# MCU089B_AltRouting_Misc.net
KiCad netlist of a schematic drawn in Altium Designer
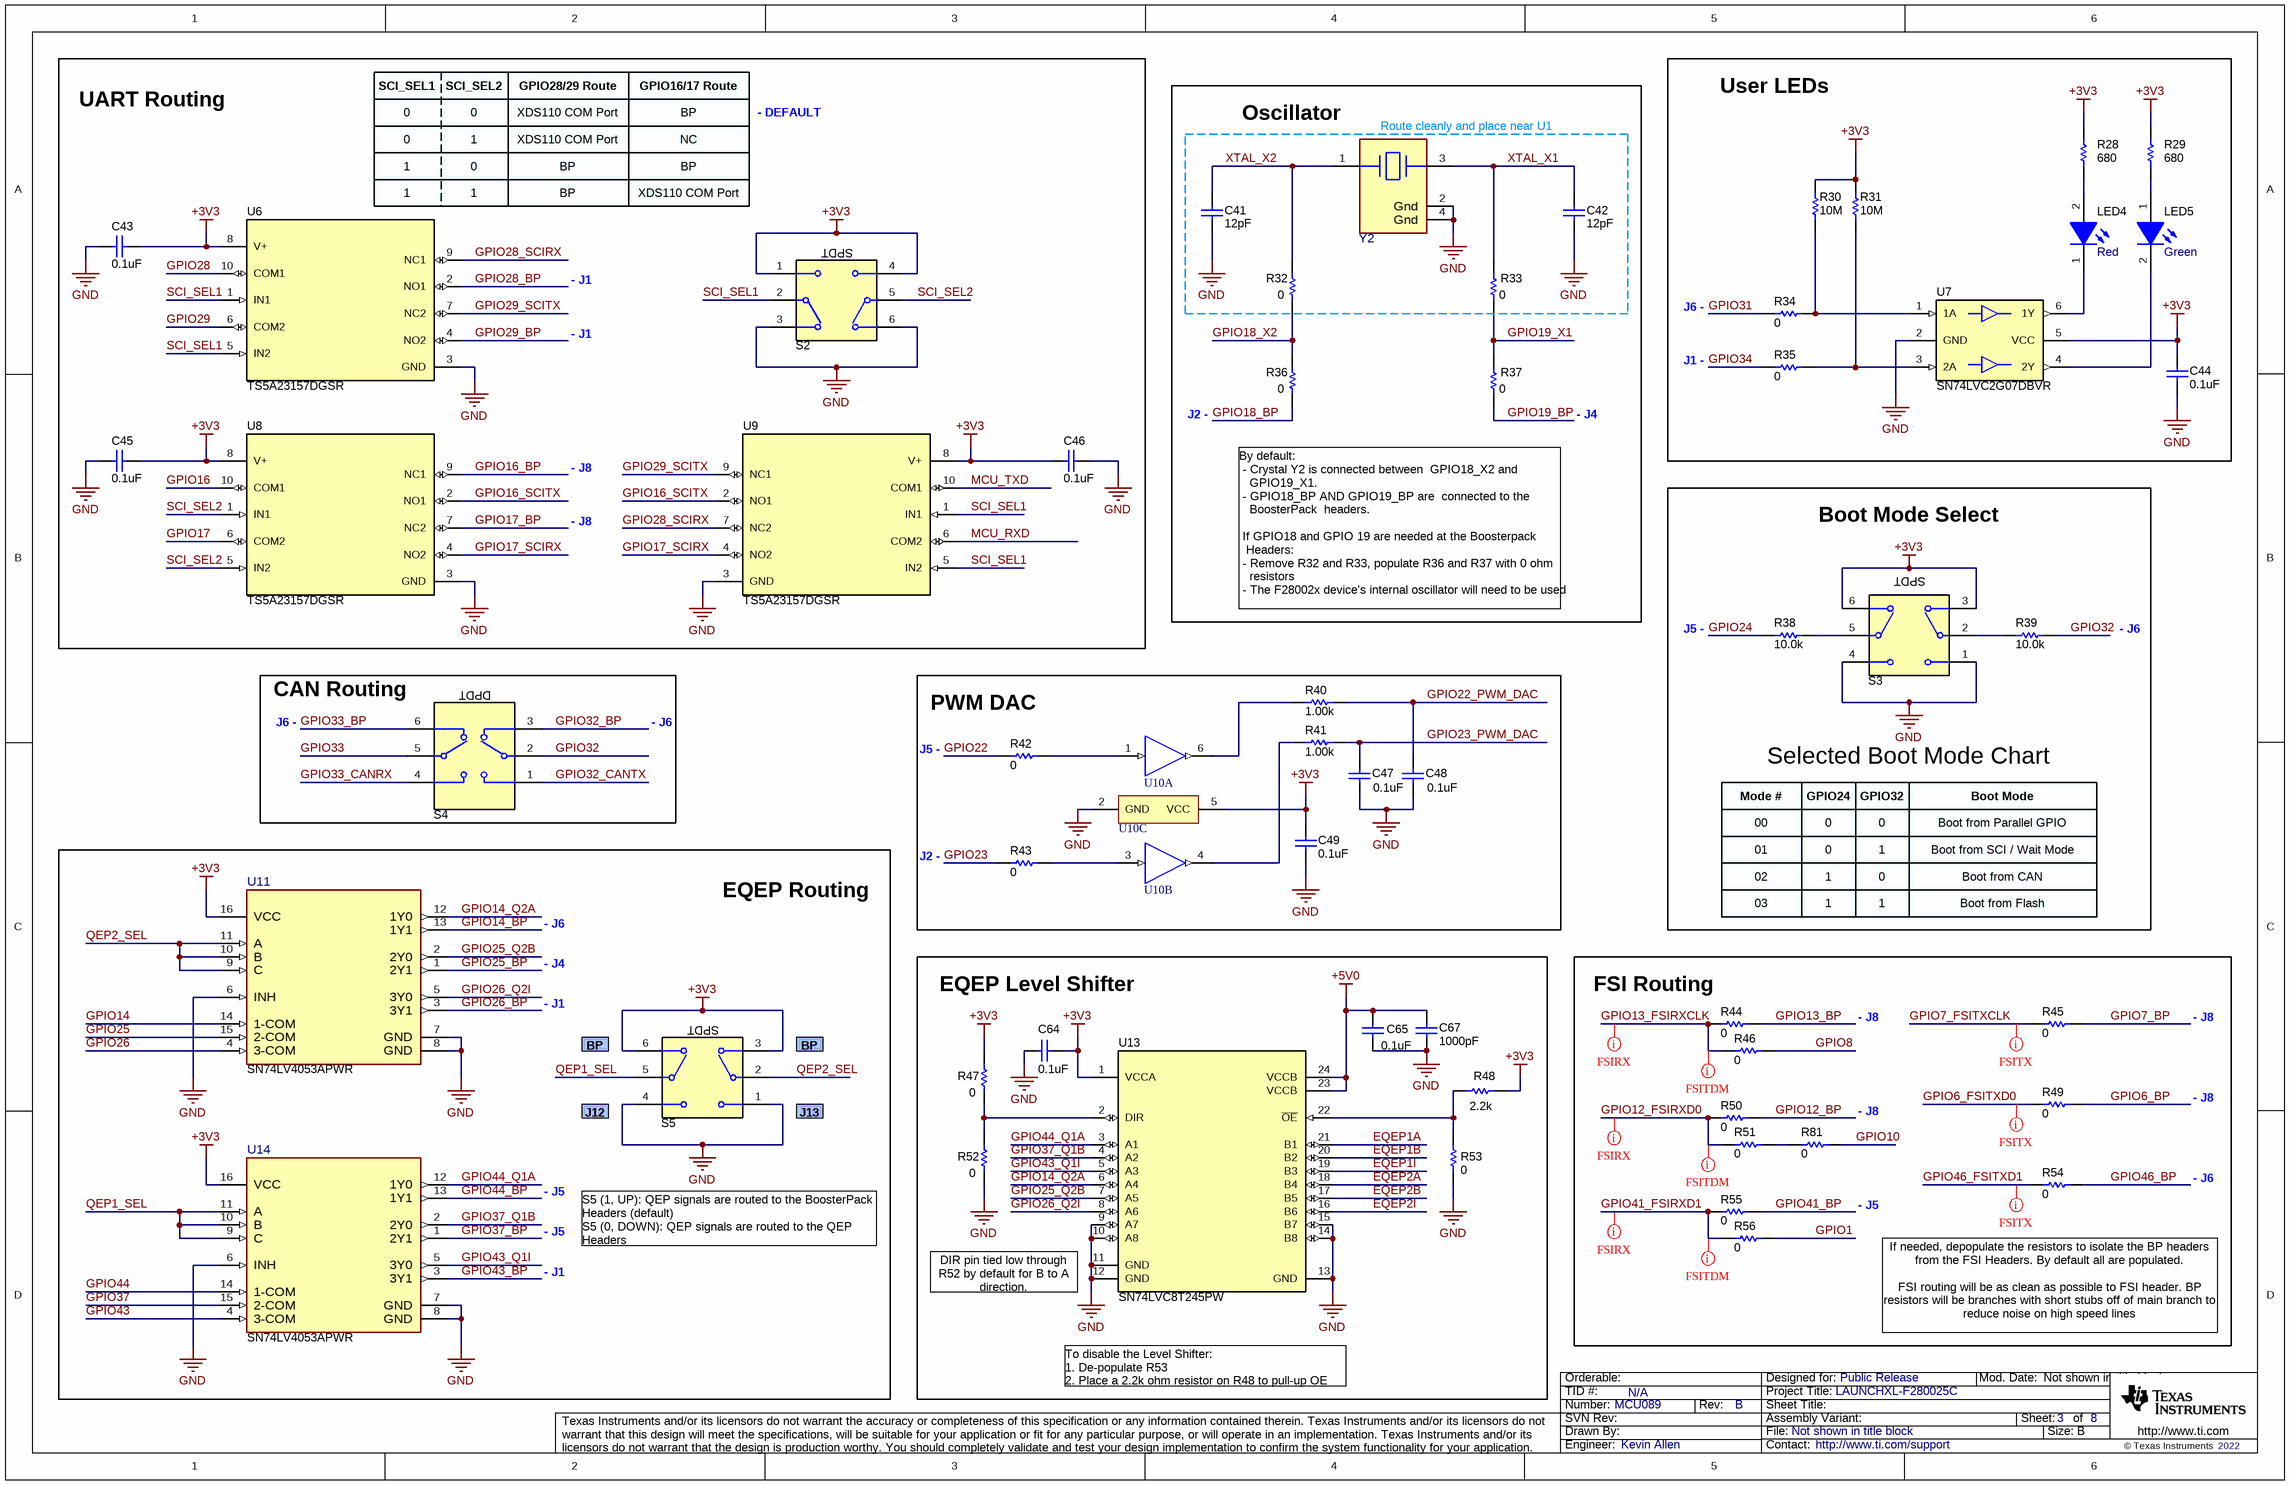
[diagram p0: MCU089B_AltRouting_Misc.SchDoc]

(export (version "E")
  (design (tool "Eeschema 10.0.6"))
  (components
    (comp (ref "C41")
      (value "C0402C120J3GACAUTO")
      (footprint "0402")
      (description "CAP, CERM, 12 pF, 25 V, +/- 5%, C0G/NP0, AEC-Q200 Grade 1, 0402")
      (fields
        (field (name "MANUFACTURER") "Kemet")
        (field (name "VALUEDISPLAYED") "12pF")
        (field (name "PUBLISHER") "Texas Instruments")
      )
      (libsource (lib "Altium Vault - TI") (part "Capacitor"))
    )
    (comp (ref "C42")
      (value "C0402C120J3GACAUTO")
      (footprint "0402")
      (description "CAP, CERM, 12 pF, 25 V, +/- 5%, C0G/NP0, AEC-Q200 Grade 1, 0402")
      (fields
        (field (name "MANUFACTURER") "Kemet")
        (field (name "VALUEDISPLAYED") "12pF")
        (field (name "PUBLISHER") "Texas Instruments")
      )
      (libsource (lib "Altium Vault - TI") (part "Capacitor"))
    )
    (comp (ref "C43")
      (value "GRM155R71A104KA01D")
      (footprint "0402")
      (description "CAP, CERM, 0.1 uF, 10 V, +/- 10%, X7R, 0402")
      (fields
        (field (name "VALUEDISPLAYED") "0.1uF")
        (field (name "MANUFACTURER") "MuRata")
        (field (name "PUBLISHER") "Texas Instruments")
      )
      (libsource (lib "Altium Vault - TI") (part "Capacitor"))
    )
    (comp (ref "C44")
      (value "GRM155R71A104KA01D")
      (footprint "0402")
      (description "CAP, CERM, 0.1 uF, 10 V, +/- 10%, X7R, 0402")
      (fields
        (field (name "VALUEDISPLAYED") "0.1uF")
        (field (name "MANUFACTURER") "MuRata")
        (field (name "PUBLISHER") "Texas Instruments")
      )
      (libsource (lib "Altium Vault - TI") (part "Capacitor"))
    )
    (comp (ref "C45")
      (value "GRM155R71A104KA01D")
      (footprint "0402")
      (description "CAP, CERM, 0.1 uF, 10 V, +/- 10%, X7R, 0402")
      (fields
        (field (name "VALUEDISPLAYED") "0.1uF")
        (field (name "MANUFACTURER") "MuRata")
        (field (name "PUBLISHER") "Texas Instruments")
      )
      (libsource (lib "Altium Vault - TI") (part "Capacitor"))
    )
    (comp (ref "C46")
      (value "GRM155R71A104KA01D")
      (footprint "0402")
      (description "CAP, CERM, 0.1 uF, 10 V, +/- 10%, X7R, 0402")
      (fields
        (field (name "VALUEDISPLAYED") "0.1uF")
        (field (name "MANUFACTURER") "MuRata")
        (field (name "PUBLISHER") "Texas Instruments")
      )
      (libsource (lib "Altium Vault - TI") (part "Capacitor"))
    )
    (comp (ref "C47")
      (value "TMK105B7104MV-FR")
      (footprint "0402")
      (description "CAP, CERM, 0.1 uF, 25 V, +/- 20%, X7R, 0402")
      (fields
        (field (name "MANUFACTURER") "Taiyo Yuden")
        (field (name "VALUEDISPLAYED") "0.1uF")
        (field (name "PUBLISHER") "Texas Instruments")
      )
      (libsource (lib "Altium Vault - TI") (part "Capacitor"))
    )
    (comp (ref "C48")
      (value "TMK105B7104MV-FR")
      (footprint "0402")
      (description "CAP, CERM, 0.1 uF, 25 V, +/- 20%, X7R, 0402")
      (fields
        (field (name "MANUFACTURER") "Taiyo Yuden")
        (field (name "VALUEDISPLAYED") "0.1uF")
        (field (name "PUBLISHER") "Texas Instruments")
      )
      (libsource (lib "Altium Vault - TI") (part "Capacitor"))
    )
    (comp (ref "C49")
      (value "GRM155R71A104KA01D")
      (footprint "0402")
      (description "CAP, CERM, 0.1 uF, 10 V, +/- 10%, X7R, 0402")
      (fields
        (field (name "VALUEDISPLAYED") "0.1uF")
        (field (name "MANUFACTURER") "MuRata")
        (field (name "PUBLISHER") "Texas Instruments")
      )
      (libsource (lib "Altium Vault - TI") (part "Capacitor"))
    )
    (comp (ref "C64")
      (value "GRM155R71A104KA01D")
      (footprint "0402")
      (description "CAP, CERM, 0.1 uF, 10 V, +/- 10%, X7R, 0402")
      (fields
        (field (name "VALUEDISPLAYED") "0.1uF")
        (field (name "MANUFACTURER") "MuRata")
        (field (name "PUBLISHER") "Texas Instruments")
      )
      (libsource (lib "Altium Vault - TI") (part "Capacitor"))
    )
    (comp (ref "C65")
      (value "GRM155R71A104KA01D")
      (footprint "0402")
      (description "CAP, CERM, 0.1 uF, 10 V, +/- 10%, X7R, 0402")
      (fields
        (field (name "VALUEDISPLAYED") "0.1uF")
        (field (name "MANUFACTURER") "MuRata")
        (field (name "PUBLISHER") "Texas Instruments")
      )
      (libsource (lib "Altium Vault - TI") (part "Capacitor"))
    )
    (comp (ref "C67")
      (value "885012205061")
      (footprint "0402")
      (description "CAP, CERM, 1000 pF, 50 V, +/- 10%, X7R, 0402")
      (fields
        (field (name "VALUEDISPLAYED") "1000pF")
        (field (name "MANUFACTURER") "Wurth Elektronik")
        (field (name "PUBLISHER") "Texas Instruments")
      )
      (libsource (lib "Altium Vault - TI") (part "Capacitor"))
    )
    (comp (ref "LED4")
      (value "Red")
      (footprint "WL-SMCW_RED_0805")
      (description "LED, Red, SMD")
      (fields (field (name "MANUFACTURER") "Wurth Elektronik") (field (name "PARTNUMBER") "150080SS75000"))
      (libsource (lib "Altium Vault - TI") (part "LED_A2_K1"))
    )
    (comp (ref "LED5")
      (value "Green")
      (footprint "LED_LTST-C171")
      (description "LED, Green, SMD")
      (fields (field (name "MANUFACTURER") "Lite-On") (field (name "PARTNUMBER") "LTST-C171GKT"))
      (libsource (lib "Altium Vault - TI") (part "LED"))
    )
    (comp (ref "R28")
      (value "CRCW0402680RJNED")
      (footprint "0402")
      (description "RES, 680, 5%, 0.063 W, AEC-Q200 Grade 0, 0402")
      (fields (field (name "MANUFACTURER") "Vishay-Dale") (field (name "VALUEDISPLAYED") "680"))
      (libsource (lib "Altium Vault - TI") (part "CMP-0026962-3"))
    )
    (comp (ref "R29")
      (value "CRCW0402680RJNED")
      (footprint "0402")
      (description "RES, 680, 5%, 0.063 W, AEC-Q200 Grade 0, 0402")
      (fields (field (name "MANUFACTURER") "Vishay-Dale") (field (name "VALUEDISPLAYED") "680"))
      (libsource (lib "Altium Vault - TI") (part "CMP-0026962-3"))
    )
    (comp (ref "R30")
      (value "CRCW040210M0JNED")
      (footprint "0402")
      (description "RES, 10 M, 5%, 0.063 W, AEC-Q200 Grade 0, 0402")
      (fields (field (name "VALUEDISPLAYED") "10M") (field (name "MANUFACTURER") "Vishay-Dale"))
      (libsource (lib "Altium Vault - TI") (part "Resistor"))
    )
    (comp (ref "R31")
      (value "CRCW040210M0JNED")
      (footprint "0402")
      (description "RES, 10 M, 5%, 0.063 W, AEC-Q200 Grade 0, 0402")
      (fields (field (name "VALUEDISPLAYED") "10M") (field (name "MANUFACTURER") "Vishay-Dale"))
      (libsource (lib "Altium Vault - TI") (part "Resistor"))
    )
    (comp (ref "R32")
      (value "CRCW06030000Z0EA")
      (footprint "0603")
      (description "RES, 0, 5%, 0.1 W, AEC-Q200 Grade 0, 0603")
      (fields (field (name "VALUEDISPLAYED") "0") (field (name "MANUFACTURER") "Vishay-Dale"))
      (libsource (lib "Altium Vault - TI") (part "Resistor"))
    )
    (comp (ref "R33")
      (value "CRCW06030000Z0EA")
      (footprint "0603")
      (description "RES, 0, 5%, 0.1 W, AEC-Q200 Grade 0, 0603")
      (fields (field (name "VALUEDISPLAYED") "0") (field (name "MANUFACTURER") "Vishay-Dale"))
      (libsource (lib "Altium Vault - TI") (part "Resistor"))
    )
    (comp (ref "R34")
      (value "CRCW06030000Z0EA")
      (footprint "0603")
      (description "RES, 0, 5%, 0.1 W, AEC-Q200 Grade 0, 0603")
      (fields (field (name "VALUEDISPLAYED") "0") (field (name "MANUFACTURER") "Vishay-Dale"))
      (libsource (lib "Altium Vault - TI") (part "Resistor"))
    )
    (comp (ref "R35")
      (value "CRCW06030000Z0EA")
      (footprint "0603")
      (description "RES, 0, 5%, 0.1 W, AEC-Q200 Grade 0, 0603")
      (fields (field (name "VALUEDISPLAYED") "0") (field (name "MANUFACTURER") "Vishay-Dale"))
      (libsource (lib "Altium Vault - TI") (part "Resistor"))
    )
    (comp (ref "R36")
      (value "CRCW06030000Z0EA")
      (footprint "0603")
      (description "RES, 0, 5%, 0.1 W, AEC-Q200 Grade 0, 0603")
      (fields (field (name "VALUEDISPLAYED") "0") (field (name "MANUFACTURER") "Vishay-Dale"))
      (libsource (lib "Altium Vault - TI") (part "Resistor"))
    )
    (comp (ref "R37")
      (value "CRCW06030000Z0EA")
      (footprint "0603")
      (description "RES, 0, 5%, 0.1 W, AEC-Q200 Grade 0, 0603")
      (fields (field (name "VALUEDISPLAYED") "0") (field (name "MANUFACTURER") "Vishay-Dale"))
      (libsource (lib "Altium Vault - TI") (part "Resistor"))
    )
    (comp (ref "R38")
      (value "RC0603FR-0710KL")
      (footprint "0603")
      (description "RES, 10.0 k, 1%, 0.1 W, 0603")
      (fields (field (name "MANUFACTURER") "Yageo") (field (name "VALUEDISPLAYED") "10.0k"))
      (libsource (lib "Altium Vault - TI") (part "Resistor"))
    )
    (comp (ref "R39")
      (value "RC0603FR-0710KL")
      (footprint "0603")
      (description "RES, 10.0 k, 1%, 0.1 W, 0603")
      (fields (field (name "MANUFACTURER") "Yageo") (field (name "VALUEDISPLAYED") "10.0k"))
      (libsource (lib "Altium Vault - TI") (part "Resistor"))
    )
    (comp (ref "R40")
      (value "CRCW04021K00FKED")
      (footprint "0402")
      (description "RES, 1.00 k, 1%, 0.063 W, AEC-Q200 Grade 0, 0402")
      (fields (field (name "MANUFACTURER") "Vishay-Dale") (field (name "VALUEDISPLAYED") "1.00k"))
      (libsource (lib "Altium Vault - TI") (part "Resistor"))
    )
    (comp (ref "R41")
      (value "CRCW04021K00FKED")
      (footprint "0402")
      (description "RES, 1.00 k, 1%, 0.063 W, AEC-Q200 Grade 0, 0402")
      (fields (field (name "MANUFACTURER") "Vishay-Dale") (field (name "VALUEDISPLAYED") "1.00k"))
      (libsource (lib "Altium Vault - TI") (part "Resistor"))
    )
    (comp (ref "R42")
      (value "CRCW06030000Z0EA")
      (footprint "0603")
      (description "RES, 0, 5%, 0.1 W, AEC-Q200 Grade 0, 0603")
      (fields (field (name "VALUEDISPLAYED") "0") (field (name "MANUFACTURER") "Vishay-Dale"))
      (libsource (lib "Altium Vault - TI") (part "Resistor"))
    )
    (comp (ref "R43")
      (value "CRCW06030000Z0EA")
      (footprint "0603")
      (description "RES, 0, 5%, 0.1 W, AEC-Q200 Grade 0, 0603")
      (fields (field (name "VALUEDISPLAYED") "0") (field (name "MANUFACTURER") "Vishay-Dale"))
      (libsource (lib "Altium Vault - TI") (part "Resistor"))
    )
    (comp (ref "R44")
      (value "CRCW06030000Z0EA")
      (footprint "0603")
      (description "RES, 0, 5%, 0.1 W, AEC-Q200 Grade 0, 0603")
      (fields (field (name "VALUEDISPLAYED") "0") (field (name "MANUFACTURER") "Vishay-Dale"))
      (libsource (lib "Altium Vault - TI") (part "Resistor"))
    )
    (comp (ref "R45")
      (value "CRCW06030000Z0EA")
      (footprint "0603")
      (description "RES, 0, 5%, 0.1 W, AEC-Q200 Grade 0, 0603")
      (fields (field (name "VALUEDISPLAYED") "0") (field (name "MANUFACTURER") "Vishay-Dale"))
      (libsource (lib "Altium Vault - TI") (part "Resistor"))
    )
    (comp (ref "R46")
      (value "CRCW06030000Z0EA")
      (footprint "0603")
      (description "RES, 0, 5%, 0.1 W, AEC-Q200 Grade 0, 0603")
      (fields (field (name "VALUEDISPLAYED") "0") (field (name "MANUFACTURER") "Vishay-Dale"))
      (libsource (lib "Altium Vault - TI") (part "Resistor"))
    )
    (comp (ref "R47")
      (value "CRCW06030000Z0EA")
      (footprint "0603")
      (description "RES, 0, 5%, 0.1 W, AEC-Q200 Grade 0, 0603")
      (fields (field (name "VALUEDISPLAYED") "0") (field (name "MANUFACTURER") "Vishay-Dale"))
      (libsource (lib "Altium Vault - TI") (part "Resistor"))
    )
    (comp (ref "R48")
      (value "CRCW06032K20JNEA")
      (footprint "0603")
      (description "RES, 2.2 k, 5%, 0.1 W, AEC-Q200 Grade 0, 0603")
      (fields (field (name "VALUEDISPLAYED") "2.2k") (field (name "MANUFACTURER") "Vishay-Dale"))
      (libsource (lib "Altium Vault - TI") (part "Resistor"))
    )
    (comp (ref "R49")
      (value "CRCW06030000Z0EA")
      (footprint "0603")
      (description "RES, 0, 5%, 0.1 W, AEC-Q200 Grade 0, 0603")
      (fields (field (name "VALUEDISPLAYED") "0") (field (name "MANUFACTURER") "Vishay-Dale"))
      (libsource (lib "Altium Vault - TI") (part "Resistor"))
    )
    (comp (ref "R50")
      (value "CRCW06030000Z0EA")
      (footprint "0603")
      (description "RES, 0, 5%, 0.1 W, AEC-Q200 Grade 0, 0603")
      (fields (field (name "VALUEDISPLAYED") "0") (field (name "MANUFACTURER") "Vishay-Dale"))
      (libsource (lib "Altium Vault - TI") (part "Resistor"))
    )
    (comp (ref "R51")
      (value "CRCW06030000Z0EA")
      (footprint "0603")
      (description "RES, 0, 5%, 0.1 W, AEC-Q200 Grade 0, 0603")
      (fields (field (name "VALUEDISPLAYED") "0") (field (name "MANUFACTURER") "Vishay-Dale"))
      (libsource (lib "Altium Vault - TI") (part "Resistor"))
    )
    (comp (ref "R52")
      (value "CRCW06030000Z0EA")
      (footprint "0603")
      (description "RES, 0, 5%, 0.1 W, AEC-Q200 Grade 0, 0603")
      (fields (field (name "VALUEDISPLAYED") "0") (field (name "MANUFACTURER") "Vishay-Dale"))
      (libsource (lib "Altium Vault - TI") (part "Resistor"))
    )
    (comp (ref "R53")
      (value "CRCW06030000Z0EA")
      (footprint "0603")
      (description "RES, 0, 5%, 0.1 W, AEC-Q200 Grade 0, 0603")
      (fields (field (name "VALUEDISPLAYED") "0") (field (name "MANUFACTURER") "Vishay-Dale"))
      (libsource (lib "Altium Vault - TI") (part "Resistor"))
    )
    (comp (ref "R54")
      (value "CRCW06030000Z0EA")
      (footprint "0603")
      (description "RES, 0, 5%, 0.1 W, AEC-Q200 Grade 0, 0603")
      (fields (field (name "VALUEDISPLAYED") "0") (field (name "MANUFACTURER") "Vishay-Dale"))
      (libsource (lib "Altium Vault - TI") (part "Resistor"))
    )
    (comp (ref "R55")
      (value "CRCW06030000Z0EA")
      (footprint "0603")
      (description "RES, 0, 5%, 0.1 W, AEC-Q200 Grade 0, 0603")
      (fields (field (name "VALUEDISPLAYED") "0") (field (name "MANUFACTURER") "Vishay-Dale"))
      (libsource (lib "Altium Vault - TI") (part "Resistor"))
    )
    (comp (ref "R56")
      (value "CRCW06030000Z0EA")
      (footprint "0603")
      (description "RES, 0, 5%, 0.1 W, AEC-Q200 Grade 0, 0603")
      (fields (field (name "VALUEDISPLAYED") "0") (field (name "MANUFACTURER") "Vishay-Dale"))
      (libsource (lib "Altium Vault - TI") (part "Resistor"))
    )
    (comp (ref "R81")
      (value "CRCW06030000Z0EA")
      (footprint "0603")
      (description "RES, 0, 5%, 0.1 W, AEC-Q200 Grade 0, 0603")
      (fields (field (name "VALUEDISPLAYED") "0") (field (name "MANUFACTURER") "Vishay-Dale"))
      (libsource (lib "Altium Vault - TI") (part "Resistor"))
    )
    (comp (ref "S2")
      (value "CAS-D20TA")
      (footprint "SW_CAS-D20TA")
      (description "Switch, Dual SPDT,  2 Pos, 0.1A, 6VDC, SMD")
      (fields
        (field (name "MANUFACTURER") "Copal Electronics")
        (field (name "PUBLISHER") "Texas Instruments")
      )
      (libsource (lib "Altium Vault - TI") (part "SW_SPDT_CAS-D20TA"))
    )
    (comp (ref "S3")
      (value "CAS-D20TA")
      (footprint "SW_CAS-D20TA")
      (description "Switch, Dual SPDT,  2 Pos, 0.1A, 6VDC, SMD")
      (fields
        (field (name "MANUFACTURER") "Copal Electronics")
        (field (name "PUBLISHER") "Texas Instruments")
      )
      (libsource (lib "") (part "SW_SPDT_CAS-D20TA_1"))
    )
    (comp (ref "S4")
      (value "CAS-220TA")
      (footprint "SW_CAS-220TA")
      (description "SLIDE SWITCH DPDT  .1A, SMT")
      (fields
        (field (name "MANUFACTURER") "Copal Electronics")
        (field (name "PUBLISHER") "Texas Instruments")
      )
      (libsource (lib "Altium Vault - TI") (part "SW_CAS-220TA"))
    )
    (comp (ref "S5")
      (value "CAS-D20TA")
      (footprint "SW_CAS-D20TA")
      (description "Switch, Dual SPDT,  2 Pos, 0.1A, 6VDC, SMD")
      (fields
        (field (name "MANUFACTURER") "Copal Electronics")
        (field (name "PUBLISHER") "Texas Instruments")
      )
      (libsource (lib "") (part "SW_SPDT_CAS-D20TA_1"))
    )
    (comp (ref "U6")
      (value "TS5A23157DGSR")
      (footprint "DGS0010A_N")
      (description "DUAL 10-Ohm SPDT ANALOG SWITCH, DGS0010A (VSSOP-10)")
      (fields
        (field (name "ALTERNATE PARTNUMBER") "TS5A23157DGST")
        (field (name "MANUFACTURER") "Texas Instruments")
        (field (name "PARTNUMBER") "TS5A23157DGSR")
        (field (name "PUBLISHER") "Texas Instruments")
      )
      (libsource (lib "Altium Vault - TI") (part "TS5A23159"))
    )
    (comp (ref "U7")
      (value "SN74LVC2G07DBVR")
      (footprint "DBV0006A_N")
      (description "Dual Buffer/Driver with Open-Drain Output, DBV0006A, LARGE T&R")
      (fields
        (field (name "GENERIC PART NUMBER") "SN74LVC2G07")
        (field (name "MANUFACTURER") "Texas Instruments")
      )
      (libsource (lib "Altium Vault - TI") (part "CMP-0051789-2"))
    )
    (comp (ref "U8")
      (value "TS5A23157DGSR")
      (footprint "DGS0010A_N")
      (description "DUAL 10-Ohm SPDT ANALOG SWITCH, DGS0010A (VSSOP-10)")
      (fields
        (field (name "ALTERNATE PARTNUMBER") "TS5A23157DGST")
        (field (name "MANUFACTURER") "Texas Instruments")
        (field (name "PARTNUMBER") "TS5A23157DGSR")
        (field (name "PUBLISHER") "Texas Instruments")
      )
      (libsource (lib "Altium Vault - TI") (part "TS5A23159"))
    )
    (comp (ref "U9")
      (value "TS5A23157DGSR")
      (footprint "DGS0010A_N")
      (description "DUAL 10-Ohm SPDT ANALOG SWITCH, DGS0010A (VSSOP-10)")
      (fields
        (field (name "ALTERNATE PARTNUMBER") "TS5A23157DGST")
        (field (name "MANUFACTURER") "Texas Instruments")
        (field (name "PARTNUMBER") "TS5A23157DGSR")
        (field (name "PUBLISHER") "Texas Instruments")
      )
      (libsource (lib "") (part "TS5A23159_1"))
    )
    (comp (ref "U10")
      (value "SN74LVC2G34DBVR")
      (footprint "DBV0006A_N")
      (description "Dual Buffer Gate, DBV0006A, LARGE T&R")
      (fields
        (field (name "MANUFACTURER") "Texas Instruments")
        (field (name "GENERIC PART NUMBER") "SN74LVC2G34")
      )
      (libsource (lib "") (part "TI-SN74XXX2GXXX-6_A_1"))
    )
    (comp (ref "U11")
      (value "SN74LV4053APWR")
      (footprint "PW0016A-MFG")
      (description "3 Circuit IC Switch 2:1 75Ohm 16-TSSOP")
      (fields
        (field (name "PARTNUMBER") "SN74LV4053APWR")
        (field (name "MOUSER PART NUMBER") "595-SN74LV4053APWR")
        (field (name "DIGIKEY PART NUMBER") "296-3833-1-ND")
      )
      (libsource (lib "Altium Vault - TI") (part "SYM-SN74LV4053APWR"))
    )
    (comp (ref "U13")
      (value "SN74LVC8T245PW")
      (footprint "PW0024A_N")
      (fields (field (name "MANUFACTURER") "Texas Instruments") (field (name "PARTNUMBER") "SN74LVC8T245PW"))
      (libsource (lib "Altium Vault - TI") (part "SN74LVC8T245"))
    )
    (comp (ref "U14")
      (value "SN74LV4053APWR")
      (footprint "PW0016A-MFG")
      (description "3 Circuit IC Switch 2:1 75Ohm 16-TSSOP")
      (fields
        (field (name "PARTNUMBER") "SN74LV4053APWR")
        (field (name "MOUSER PART NUMBER") "595-SN74LV4053APWR")
        (field (name "DIGIKEY PART NUMBER") "296-3833-1-ND")
      )
      (libsource (lib "Altium Vault - TI") (part "SYM-SN74LV4053APWR"))
    )
    (comp (ref "Y2")
      (value "ECS-200-8-30B-CKM")
      (footprint "FP-ECS-200-8-30B-CKM_SMD4-MFG")
      (description "20 MHz ±10ppm Crystal 8pF 40 Ohms 4-SMD, No Lead")
      (fields
        (field (name "MOUSER PART NUMBER") "520-200-8-30B-CKM")
        (field (name "MANUFACTURER") "ECS International")
      )
      (libsource (lib "Altium Vault - TI") (part "SYM-ECS-200-8-30B-CKM"))
    )
  )
  (nets
    (net (code "1") (name "+3V3") (class "Default")
      (node (ref "C43") (pin "1") (pinfunction "1_1") (pintype "passive"))
      (node (ref "C44") (pin "2") (pinfunction "2_2") (pintype "passive"))
      (node (ref "C45") (pin "1") (pinfunction "1_1") (pintype "passive"))
      (node (ref "C46") (pin "2") (pinfunction "2_2") (pintype "passive"))
      (node (ref "C49") (pin "2") (pinfunction "2_2") (pintype "passive"))
      (node (ref "C64") (pin "1") (pinfunction "1_1") (pintype "passive"))
      (node (ref "R28") (pin "2") (pinfunction "2_2") (pintype "passive"))
      (node (ref "R29") (pin "2") (pinfunction "2_2") (pintype "passive"))
      (node (ref "R30") (pin "2") (pinfunction "2_2") (pintype "passive"))
      (node (ref "R31") (pin "2") (pinfunction "2_2") (pintype "passive"))
      (node (ref "R47") (pin "2") (pinfunction "2_2") (pintype "passive"))
      (node (ref "R48") (pin "2") (pinfunction "2_2") (pintype "passive"))
      (node (ref "S2") (pin "1") (pinfunction "1_1") (pintype "passive"))
      (node (ref "S2") (pin "4") (pinfunction "4_4") (pintype "passive"))
      (node (ref "S3") (pin "3") (pinfunction "3_3") (pintype "passive"))
      (node (ref "S3") (pin "6") (pinfunction "6_6") (pintype "passive"))
      (node (ref "S5") (pin "3") (pinfunction "3_3") (pintype "passive"))
      (node (ref "S5") (pin "6") (pinfunction "6_6") (pintype "passive"))
      (node (ref "U10") (pin "5") (pinfunction "VCC_5") (pintype "power_in"))
      (node (ref "U11") (pin "16") (pinfunction "VCC_16") (pintype "power_in"))
      (node (ref "U13") (pin "1") (pinfunction "VCCA_1") (pintype "power_in"))
      (node (ref "U14") (pin "16") (pinfunction "VCC_16") (pintype "power_in"))
      (node (ref "U6") (pin "8") (pinfunction "V+_8") (pintype "power_in"))
      (node (ref "U7") (pin "5") (pinfunction "VCC_5") (pintype "power_in"))
      (node (ref "U8") (pin "8") (pinfunction "V+_8") (pintype "power_in"))
      (node (ref "U9") (pin "8") (pinfunction "V+_8") (pintype "power_in"))
    )
    (net (code "2") (name "+5V0") (class "Default")
      (node (ref "C65") (pin "2") (pinfunction "2_2") (pintype "passive"))
      (node (ref "C67") (pin "1") (pinfunction "1_1") (pintype "passive"))
      (node (ref "U13") (pin "23") (pinfunction "VCCB_23") (pintype "power_in"))
      (node (ref "U13") (pin "24") (pinfunction "VCCB_24") (pintype "power_in"))
    )
    (net (code "3") (name "/EQEP1A") (class "Default")
      (node (ref "U13") (pin "21") (pinfunction "B1_21") (pintype "bidirectional"))
    )
    (net (code "4") (name "/EQEP1B") (class "Default")
      (node (ref "U13") (pin "20") (pinfunction "B2_20") (pintype "bidirectional"))
    )
    (net (code "5") (name "/EQEP1I") (class "Default")
      (node (ref "U13") (pin "19") (pinfunction "B3_19") (pintype "bidirectional"))
    )
    (net (code "6") (name "/EQEP2A") (class "Default")
      (node (ref "U13") (pin "18") (pinfunction "B4_18") (pintype "bidirectional"))
    )
    (net (code "7") (name "/EQEP2B") (class "Default")
      (node (ref "U13") (pin "17") (pinfunction "B5_17") (pintype "bidirectional"))
    )
    (net (code "8") (name "/EQEP2I") (class "Default")
      (node (ref "U13") (pin "16") (pinfunction "B6_16") (pintype "bidirectional"))
    )
    (net (code "9") (name "/GPIO1") (class "Default")
      (node (ref "R56") (pin "2") (pinfunction "2_2") (pintype "passive"))
    )
    (net (code "10") (name "/GPIO6_BP") (class "Default")
      (node (ref "R49") (pin "2") (pinfunction "2_2") (pintype "passive"))
    )
    (net (code "11") (name "/GPIO6_FSITXD0") (class "Default")
      (node (ref "R49") (pin "1") (pinfunction "1_1") (pintype "passive"))
    )
    (net (code "12") (name "/GPIO7_BP") (class "Default")
      (node (ref "R45") (pin "2") (pinfunction "2_2") (pintype "passive"))
    )
    (net (code "13") (name "/GPIO7_FSITXCLK") (class "Default")
      (node (ref "R45") (pin "1") (pinfunction "1_1") (pintype "passive"))
    )
    (net (code "14") (name "/GPIO8") (class "Default")
      (node (ref "R46") (pin "2") (pinfunction "2_2") (pintype "passive"))
    )
    (net (code "15") (name "/GPIO10") (class "Default")
      (node (ref "R81") (pin "2") (pinfunction "2_2") (pintype "passive"))
    )
    (net (code "16") (name "/GPIO12_BP") (class "Default")
      (node (ref "R50") (pin "2") (pinfunction "2_2") (pintype "passive"))
    )
    (net (code "17") (name "/GPIO12_FSIRXD0") (class "Default")
      (node (ref "R50") (pin "1") (pinfunction "1_1") (pintype "passive"))
      (node (ref "R51") (pin "1") (pinfunction "1_1") (pintype "passive"))
    )
    (net (code "18") (name "/GPIO13_BP") (class "Default")
      (node (ref "R44") (pin "2") (pinfunction "2_2") (pintype "passive"))
    )
    (net (code "19") (name "/GPIO13_FSIRXCLK") (class "Default")
      (node (ref "R44") (pin "1") (pinfunction "1_1") (pintype "passive"))
      (node (ref "R46") (pin "1") (pinfunction "1_1") (pintype "passive"))
    )
    (net (code "20") (name "/GPIO14") (class "Default")
      (node (ref "U11") (pin "14") (pinfunction "1-COM_14") (pintype "input"))
    )
    (net (code "21") (name "/GPIO14_BP") (class "Default")
      (node (ref "U11") (pin "13") (pinfunction "1Y1_13") (pintype "output"))
    )
    (net (code "22") (name "/GPIO14_Q2A") (class "Default")
      (node (ref "U11") (pin "12") (pinfunction "1Y0_12") (pintype "output"))
      (node (ref "U13") (pin "6") (pinfunction "A4_6") (pintype "bidirectional"))
    )
    (net (code "23") (name "/GPIO16") (class "Default")
      (node (ref "U8") (pin "10") (pinfunction "COM1_10") (pintype "bidirectional"))
    )
    (net (code "24") (name "/GPIO16_BP") (class "Default")
      (node (ref "U8") (pin "9") (pinfunction "NC1_9") (pintype "bidirectional"))
    )
    (net (code "25") (name "/GPIO16_SCITX") (class "Default")
      (node (ref "U8") (pin "2") (pinfunction "NO1_2") (pintype "bidirectional"))
      (node (ref "U9") (pin "2") (pinfunction "NO1_2") (pintype "bidirectional"))
    )
    (net (code "26") (name "/GPIO17") (class "Default")
      (node (ref "U8") (pin "6") (pinfunction "COM2_6") (pintype "bidirectional"))
    )
    (net (code "27") (name "/GPIO17_BP") (class "Default")
      (node (ref "U8") (pin "7") (pinfunction "NC2_7") (pintype "bidirectional"))
    )
    (net (code "28") (name "/GPIO17_SCIRX") (class "Default")
      (node (ref "U8") (pin "4") (pinfunction "NO2_4") (pintype "bidirectional"))
      (node (ref "U9") (pin "4") (pinfunction "NO2_4") (pintype "bidirectional"))
    )
    (net (code "29") (name "/GPIO18_BP") (class "Default")
      (node (ref "R36") (pin "1") (pinfunction "1_1") (pintype "passive"))
    )
    (net (code "30") (name "/GPIO18_X2") (class "Default")
      (node (ref "R32") (pin "1") (pinfunction "1_1") (pintype "passive"))
      (node (ref "R36") (pin "2") (pinfunction "2_2") (pintype "passive"))
    )
    (net (code "31") (name "/GPIO19_BP") (class "Default")
      (node (ref "R37") (pin "1") (pinfunction "1_1") (pintype "passive"))
    )
    (net (code "32") (name "/GPIO19_X1") (class "Default")
      (node (ref "R33") (pin "1") (pinfunction "1_1") (pintype "passive"))
      (node (ref "R37") (pin "2") (pinfunction "2_2") (pintype "passive"))
    )
    (net (code "33") (name "/GPIO22") (class "Default")
      (node (ref "R42") (pin "1") (pinfunction "1_1") (pintype "passive"))
    )
    (net (code "34") (name "/GPIO22_PWM_DAC") (class "Default")
      (node (ref "C48") (pin "1") (pinfunction "1_1") (pintype "passive"))
      (node (ref "R40") (pin "2") (pinfunction "2_2") (pintype "passive"))
    )
    (net (code "35") (name "/GPIO23") (class "Default")
      (node (ref "R43") (pin "1") (pinfunction "1_1") (pintype "passive"))
    )
    (net (code "36") (name "/GPIO23_PWM_DAC") (class "Default")
      (node (ref "C47") (pin "1") (pinfunction "1_1") (pintype "passive"))
      (node (ref "R41") (pin "2") (pinfunction "2_2") (pintype "passive"))
    )
    (net (code "37") (name "/GPIO24") (class "Default")
      (node (ref "R38") (pin "1") (pinfunction "1_1") (pintype "passive"))
    )
    (net (code "38") (name "/GPIO25") (class "Default")
      (node (ref "U11") (pin "15") (pinfunction "2-COM_15") (pintype "input"))
    )
    (net (code "39") (name "/GPIO25_BP") (class "Default")
      (node (ref "U11") (pin "1") (pinfunction "2Y1_1") (pintype "output"))
    )
    (net (code "40") (name "/GPIO25_Q2B") (class "Default")
      (node (ref "U11") (pin "2") (pinfunction "2Y0_2") (pintype "output"))
      (node (ref "U13") (pin "7") (pinfunction "A5_7") (pintype "bidirectional"))
    )
    (net (code "41") (name "/GPIO26") (class "Default")
      (node (ref "U11") (pin "4") (pinfunction "3-COM_4") (pintype "input"))
    )
    (net (code "42") (name "/GPIO26_BP") (class "Default")
      (node (ref "U11") (pin "3") (pinfunction "3Y1_3") (pintype "output"))
    )
    (net (code "43") (name "/GPIO26_Q2I") (class "Default")
      (node (ref "U11") (pin "5") (pinfunction "3Y0_5") (pintype "output"))
      (node (ref "U13") (pin "8") (pinfunction "A6_8") (pintype "bidirectional"))
    )
    (net (code "44") (name "/GPIO28") (class "Default")
      (node (ref "U6") (pin "10") (pinfunction "COM1_10") (pintype "bidirectional"))
    )
    (net (code "45") (name "/GPIO28_BP") (class "Default")
      (node (ref "U6") (pin "2") (pinfunction "NO1_2") (pintype "bidirectional"))
    )
    (net (code "46") (name "/GPIO28_SCIRX") (class "Default")
      (node (ref "U6") (pin "9") (pinfunction "NC1_9") (pintype "bidirectional"))
      (node (ref "U9") (pin "7") (pinfunction "NC2_7") (pintype "bidirectional"))
    )
    (net (code "47") (name "/GPIO29") (class "Default")
      (node (ref "U6") (pin "6") (pinfunction "COM2_6") (pintype "bidirectional"))
    )
    (net (code "48") (name "/GPIO29_BP") (class "Default")
      (node (ref "U6") (pin "4") (pinfunction "NO2_4") (pintype "bidirectional"))
    )
    (net (code "49") (name "/GPIO29_SCITX") (class "Default")
      (node (ref "U6") (pin "7") (pinfunction "NC2_7") (pintype "bidirectional"))
      (node (ref "U9") (pin "9") (pinfunction "NC1_9") (pintype "bidirectional"))
    )
    (net (code "50") (name "/GPIO31") (class "Default")
      (node (ref "R34") (pin "1") (pinfunction "1_1") (pintype "passive"))
    )
    (net (code "51") (name "/GPIO32") (class "Default")
      (node (ref "R39") (pin "2") (pinfunction "2_2") (pintype "passive"))
      (node (ref "S4") (pin "2") (pinfunction "2_2") (pintype "passive"))
    )
    (net (code "52") (name "/GPIO32_BP") (class "Default")
      (node (ref "S4") (pin "3") (pinfunction "3_3") (pintype "passive"))
    )
    (net (code "53") (name "/GPIO32_CANTX") (class "Default")
      (node (ref "S4") (pin "1") (pinfunction "1_1") (pintype "passive"))
    )
    (net (code "54") (name "/GPIO33") (class "Default")
      (node (ref "S4") (pin "5") (pinfunction "5_5") (pintype "passive"))
    )
    (net (code "55") (name "/GPIO33_BP") (class "Default")
      (node (ref "S4") (pin "6") (pinfunction "6_6") (pintype "passive"))
    )
    (net (code "56") (name "/GPIO33_CANRX") (class "Default")
      (node (ref "S4") (pin "4") (pinfunction "4_4") (pintype "passive"))
    )
    (net (code "57") (name "/GPIO34") (class "Default")
      (node (ref "R35") (pin "1") (pinfunction "1_1") (pintype "passive"))
    )
    (net (code "58") (name "/GPIO37") (class "Default")
      (node (ref "U14") (pin "15") (pinfunction "2-COM_15") (pintype "input"))
    )
    (net (code "59") (name "/GPIO37_BP") (class "Default")
      (node (ref "U14") (pin "1") (pinfunction "2Y1_1") (pintype "output"))
    )
    (net (code "60") (name "/GPIO37_Q1B") (class "Default")
      (node (ref "U13") (pin "4") (pinfunction "A2_4") (pintype "bidirectional"))
      (node (ref "U14") (pin "2") (pinfunction "2Y0_2") (pintype "output"))
    )
    (net (code "61") (name "/GPIO41_BP") (class "Default")
      (node (ref "R55") (pin "2") (pinfunction "2_2") (pintype "passive"))
    )
    (net (code "62") (name "/GPIO41_FSIRXD1") (class "Default")
      (node (ref "R55") (pin "1") (pinfunction "1_1") (pintype "passive"))
      (node (ref "R56") (pin "1") (pinfunction "1_1") (pintype "passive"))
    )
    (net (code "63") (name "/GPIO43") (class "Default")
      (node (ref "U14") (pin "4") (pinfunction "3-COM_4") (pintype "input"))
    )
    (net (code "64") (name "/GPIO43_BP") (class "Default")
      (node (ref "U14") (pin "3") (pinfunction "3Y1_3") (pintype "output"))
    )
    (net (code "65") (name "/GPIO43_Q1I") (class "Default")
      (node (ref "U13") (pin "5") (pinfunction "A3_5") (pintype "bidirectional"))
      (node (ref "U14") (pin "5") (pinfunction "3Y0_5") (pintype "output"))
    )
    (net (code "66") (name "/GPIO44") (class "Default")
      (node (ref "U14") (pin "14") (pinfunction "1-COM_14") (pintype "input"))
    )
    (net (code "67") (name "/GPIO44_BP") (class "Default")
      (node (ref "U14") (pin "13") (pinfunction "1Y1_13") (pintype "output"))
    )
    (net (code "68") (name "/GPIO44_Q1A") (class "Default")
      (node (ref "U13") (pin "3") (pinfunction "A1_3") (pintype "bidirectional"))
      (node (ref "U14") (pin "12") (pinfunction "1Y0_12") (pintype "output"))
    )
    (net (code "69") (name "/GPIO46_BP") (class "Default")
      (node (ref "R54") (pin "2") (pinfunction "2_2") (pintype "passive"))
    )
    (net (code "70") (name "/GPIO46_FSITXD1") (class "Default")
      (node (ref "R54") (pin "1") (pinfunction "1_1") (pintype "passive"))
    )
    (net (code "71") (name "/MCU_RXD") (class "Default")
      (node (ref "U9") (pin "6") (pinfunction "COM2_6") (pintype "bidirectional"))
    )
    (net (code "72") (name "/MCU_TXD") (class "Default")
      (node (ref "U9") (pin "10") (pinfunction "COM1_10") (pintype "bidirectional"))
    )
    (net (code "73") (name "/QEP1_SEL") (class "Default")
      (node (ref "S5") (pin "5") (pinfunction "C_5") (pintype "passive"))
      (node (ref "U14") (pin "10") (pinfunction "B_10") (pintype "input"))
      (node (ref "U14") (pin "11") (pinfunction "A_11") (pintype "input"))
      (node (ref "U14") (pin "9") (pinfunction "C_9") (pintype "input"))
    )
    (net (code "74") (name "/QEP2_SEL") (class "Default")
      (node (ref "S5") (pin "2") (pinfunction "C_2") (pintype "passive"))
      (node (ref "U11") (pin "10") (pinfunction "B_10") (pintype "input"))
      (node (ref "U11") (pin "11") (pinfunction "A_11") (pintype "input"))
      (node (ref "U11") (pin "9") (pinfunction "C_9") (pintype "input"))
    )
    (net (code "75") (name "/SCI_SEL1") (class "Default")
      (node (ref "S2") (pin "2") (pinfunction "C_2") (pintype "passive"))
      (node (ref "U6") (pin "1") (pinfunction "IN1_1") (pintype "input"))
      (node (ref "U6") (pin "5") (pinfunction "IN2_5") (pintype "input"))
      (node (ref "U9") (pin "1") (pinfunction "IN1_1") (pintype "input"))
      (node (ref "U9") (pin "5") (pinfunction "IN2_5") (pintype "input"))
    )
    (net (code "76") (name "/SCI_SEL2") (class "Default")
      (node (ref "S2") (pin "5") (pinfunction "C_5") (pintype "passive"))
      (node (ref "U8") (pin "1") (pinfunction "IN1_1") (pintype "input"))
      (node (ref "U8") (pin "5") (pinfunction "IN2_5") (pintype "input"))
    )
    (net (code "77") (name "/XTAL_X1") (class "Default")
      (node (ref "C42") (pin "1") (pinfunction "1_1") (pintype "passive"))
      (node (ref "R33") (pin "2") (pinfunction "2_2") (pintype "passive"))
      (node (ref "Y2") (pin "3") (pinfunction "Out/In_3") (pintype "passive"))
    )
    (net (code "78") (name "/XTAL_X2") (class "Default")
      (node (ref "C41") (pin "1") (pinfunction "1_1") (pintype "passive"))
      (node (ref "R32") (pin "2") (pinfunction "2_2") (pintype "passive"))
      (node (ref "Y2") (pin "1") (pinfunction "In/Out_1") (pintype "passive"))
    )
    (net (code "79") (name "GND") (class "Default")
      (node (ref "C41") (pin "2") (pinfunction "2_2") (pintype "passive"))
      (node (ref "C42") (pin "2") (pinfunction "2_2") (pintype "passive"))
      (node (ref "C43") (pin "2") (pinfunction "2_2") (pintype "passive"))
      (node (ref "C44") (pin "1") (pinfunction "1_1") (pintype "passive"))
      (node (ref "C45") (pin "2") (pinfunction "2_2") (pintype "passive"))
      (node (ref "C46") (pin "1") (pinfunction "1_1") (pintype "passive"))
      (node (ref "C47") (pin "2") (pinfunction "2_2") (pintype "passive"))
      (node (ref "C48") (pin "2") (pinfunction "2_2") (pintype "passive"))
      (node (ref "C49") (pin "1") (pinfunction "1_1") (pintype "passive"))
      (node (ref "C64") (pin "2") (pinfunction "2_2") (pintype "passive"))
      (node (ref "C65") (pin "1") (pinfunction "1_1") (pintype "passive"))
      (node (ref "C67") (pin "2") (pinfunction "2_2") (pintype "passive"))
      (node (ref "R52") (pin "1") (pinfunction "1_1") (pintype "passive"))
      (node (ref "R53") (pin "2") (pinfunction "2_2") (pintype "passive"))
      (node (ref "S2") (pin "3") (pinfunction "3_3") (pintype "passive"))
      (node (ref "S2") (pin "6") (pinfunction "6_6") (pintype "passive"))
      (node (ref "S3") (pin "1") (pinfunction "1_1") (pintype "passive"))
      (node (ref "S3") (pin "4") (pinfunction "4_4") (pintype "passive"))
      (node (ref "S5") (pin "1") (pinfunction "1_1") (pintype "passive"))
      (node (ref "S5") (pin "4") (pinfunction "4_4") (pintype "passive"))
      (node (ref "U10") (pin "2") (pinfunction "GND_2") (pintype "power_in"))
      (node (ref "U11") (pin "6") (pinfunction "INH_6") (pintype "input"))
      (node (ref "U11") (pin "7") (pinfunction "GND_7") (pintype "power_in"))
      (node (ref "U11") (pin "8") (pinfunction "GND_8") (pintype "power_in"))
      (node (ref "U13") (pin "10") (pinfunction "A8_10") (pintype "bidirectional"))
      (node (ref "U13") (pin "11") (pinfunction "GND_11") (pintype "power_in"))
      (node (ref "U13") (pin "12") (pinfunction "GND_12") (pintype "power_in"))
      (node (ref "U13") (pin "13") (pinfunction "GND_13") (pintype "power_in"))
      (node (ref "U13") (pin "14") (pinfunction "B8_14") (pintype "bidirectional"))
      (node (ref "U13") (pin "15") (pinfunction "B7_15") (pintype "bidirectional"))
      (node (ref "U13") (pin "9") (pinfunction "A7_9") (pintype "bidirectional"))
      (node (ref "U14") (pin "6") (pinfunction "INH_6") (pintype "input"))
      (node (ref "U14") (pin "7") (pinfunction "GND_7") (pintype "power_in"))
      (node (ref "U14") (pin "8") (pinfunction "GND_8") (pintype "power_in"))
      (node (ref "U6") (pin "3") (pinfunction "GND_3") (pintype "power_in"))
      (node (ref "U7") (pin "2") (pinfunction "GND_2") (pintype "power_in"))
      (node (ref "U8") (pin "3") (pinfunction "GND_3") (pintype "power_in"))
      (node (ref "U9") (pin "3") (pinfunction "GND_3") (pintype "power_in"))
      (node (ref "Y2") (pin "2") (pinfunction "Gnd_2") (pintype "power_in"))
      (node (ref "Y2") (pin "4") (pinfunction "Gnd_4") (pintype "power_in"))
    )
    (net (code "80") (name "Net-(LED4-A)") (class "Default")
      (node (ref "LED4") (pin "2") (pinfunction "A_2") (pintype "passive"))
      (node (ref "R28") (pin "1") (pinfunction "1_1") (pintype "passive"))
    )
    (net (code "81") (name "Net-(LED4-K)") (class "Default")
      (node (ref "LED4") (pin "1") (pinfunction "K_1") (pintype "passive"))
      (node (ref "U7") (pin "6") (pinfunction "1Y_6") (pintype "output"))
    )
    (net (code "82") (name "Net-(LED5-A)") (class "Default")
      (node (ref "LED5") (pin "1") (pinfunction "A_1") (pintype "passive"))
      (node (ref "R29") (pin "1") (pinfunction "1_1") (pintype "passive"))
    )
    (net (code "83") (name "Net-(LED5-K)") (class "Default")
      (node (ref "LED5") (pin "2") (pinfunction "K_2") (pintype "passive"))
      (node (ref "U7") (pin "4") (pinfunction "2Y_4") (pintype "output"))
    )
    (net (code "84") (name "Net-(R38-Pad2)") (class "Default")
      (node (ref "R38") (pin "2") (pinfunction "2_2") (pintype "passive"))
      (node (ref "S3") (pin "5") (pinfunction "C_5") (pintype "passive"))
    )
    (net (code "85") (name "Net-(R39-Pad1)") (class "Default")
      (node (ref "R39") (pin "1") (pinfunction "1_1") (pintype "passive"))
      (node (ref "S3") (pin "2") (pinfunction "C_2") (pintype "passive"))
    )
    (net (code "86") (name "Net-(R51-Pad2)") (class "Default")
      (node (ref "R51") (pin "2") (pinfunction "2_2") (pintype "passive"))
      (node (ref "R81") (pin "1") (pinfunction "1_1") (pintype "passive"))
    )
    (net (code "87") (name "Net-(U7-1A)") (class "Default")
      (node (ref "R30") (pin "1") (pinfunction "1_1") (pintype "passive"))
      (node (ref "R34") (pin "2") (pinfunction "2_2") (pintype "passive"))
      (node (ref "U7") (pin "1") (pinfunction "1A_1") (pintype "input"))
    )
    (net (code "88") (name "Net-(U7-2A)") (class "Default")
      (node (ref "R31") (pin "1") (pinfunction "1_1") (pintype "passive"))
      (node (ref "R35") (pin "2") (pinfunction "2_2") (pintype "passive"))
      (node (ref "U7") (pin "3") (pinfunction "2A_3") (pintype "input"))
    )
    (net (code "89") (name "Net-(U10A-1A)") (class "Default")
      (node (ref "R42") (pin "2") (pinfunction "2_2") (pintype "passive"))
      (node (ref "U10") (pin "1") (pinfunction "1A_1") (pintype "input"))
    )
    (net (code "90") (name "Net-(U10A-1Y)") (class "Default")
      (node (ref "R40") (pin "1") (pinfunction "1_1") (pintype "passive"))
      (node (ref "U10") (pin "6") (pinfunction "1Y_6") (pintype "output"))
    )
    (net (code "91") (name "Net-(U10B-2A)") (class "Default")
      (node (ref "R43") (pin "2") (pinfunction "2_2") (pintype "passive"))
      (node (ref "U10") (pin "3") (pinfunction "2A_3") (pintype "input"))
    )
    (net (code "92") (name "Net-(U10B-2Y)") (class "Default")
      (node (ref "R41") (pin "1") (pinfunction "1_1") (pintype "passive"))
      (node (ref "U10") (pin "4") (pinfunction "2Y_4") (pintype "output"))
    )
    (net (code "93") (name "Net-(U13-DIR)") (class "Default")
      (node (ref "R47") (pin "1") (pinfunction "1_1") (pintype "passive"))
      (node (ref "R52") (pin "2") (pinfunction "2_2") (pintype "passive"))
      (node (ref "U13") (pin "2") (pinfunction "DIR_2") (pintype "bidirectional"))
    )
    (net (code "94") (name "Net-(U13-OE)") (class "Default")
      (node (ref "R48") (pin "1") (pinfunction "1_1") (pintype "passive"))
      (node (ref "R53") (pin "1") (pinfunction "1_1") (pintype "passive"))
      (node (ref "U13") (pin "22") (pinfunction "OE_22") (pintype "input"))
    )
  )
)
